# Sheet1.net
KiCad netlist of a schematic drawn in Altium Designer
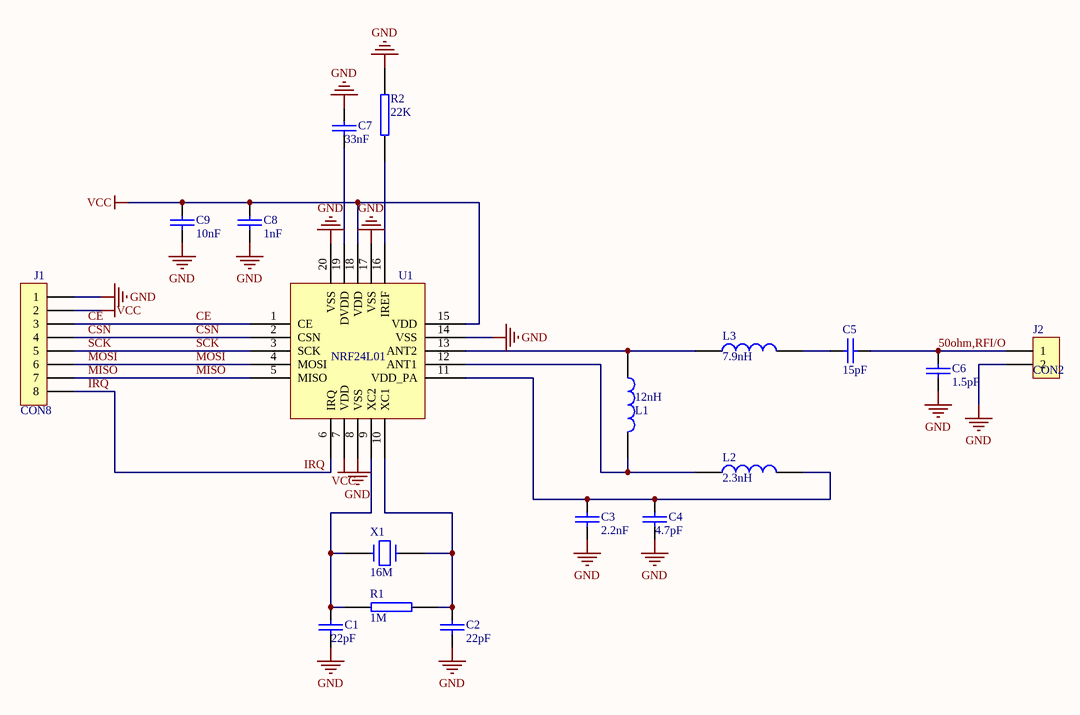
[diagram p0: Sheet1.SchDoc]

(export (version "E")
  (design (tool "Eeschema 10.0.6"))
  (components
    (comp (ref "C1")
      (value "22pF")
      (footprint "1608[0603]")
      (description "Capacitor")
      (libsource (lib "*") (part "CAP"))
    )
    (comp (ref "C2")
      (value "22pF")
      (footprint "1608[0603]")
      (description "Capacitor")
      (libsource (lib "*") (part "CAP"))
    )
    (comp (ref "C3")
      (value "2.2nF")
      (footprint "1608[0603]")
      (description "Capacitor")
      (libsource (lib "*") (part "CAP"))
    )
    (comp (ref "C4")
      (value "4.7pF")
      (footprint "1608[0603]")
      (description "Capacitor")
      (libsource (lib "*") (part "CAP"))
    )
    (comp (ref "C5")
      (value "15pF")
      (footprint "1608[0603]")
      (description "Capacitor")
      (libsource (lib "*") (part "CAP"))
    )
    (comp (ref "C6")
      (value "1.5pF")
      (footprint "1608[0603]")
      (description "Capacitor")
      (libsource (lib "*") (part "CAP"))
    )
    (comp (ref "C7")
      (value "33nF")
      (footprint "Miscellaneous Devices:1608[0603]")
      (description "Capacitor")
      (libsource (lib "*") (part "CAP"))
    )
    (comp (ref "C8")
      (value "1nF")
      (footprint "1608[0603]")
      (description "Capacitor")
      (libsource (lib "*") (part "CAP"))
    )
    (comp (ref "C9")
      (value "10nF")
      (footprint "1608[0603]")
      (description "Capacitor")
      (libsource (lib "*") (part "CAP"))
    )
    (comp (ref "J1")
      (value "CON8")
      (footprint "HDR2X4")
      (description "Connector")
      (libsource (lib "*") (part "CON8"))
    )
    (comp (ref "J2")
      (value "CON2")
      (footprint "SMA")
      (description "Connector")
      (libsource (lib "*") (part "CON2"))
    )
    (comp (ref "L1") (value "12nH") (footprint "1608[0603]") (libsource (lib "*") (part "INDUCTOR")))
    (comp (ref "L2") (value "2.3nH") (footprint "1608[0603]") (libsource (lib "*") (part "INDUCTOR")))
    (comp (ref "L3") (value "7.9nH") (footprint "1608[0603]") (libsource (lib "*") (part "INDUCTOR")))
    (comp (ref "R1") (value "1M") (footprint "1608[0603]") (libsource (lib "*") (part "RES2")))
    (comp (ref "R2") (value "22K") (footprint "1608[0603]") (libsource (lib "*") (part "RES2")))
    (comp (ref "U1") (value "NRF24L01") (footprint "传感器fsc:wifi") (libsource (lib "*") (part "NRF24L01")))
    (comp (ref "X1")
      (value "16M")
      (footprint "传感器fsc:jingzhen")
      (description "Crystal")
      (libsource (lib "*") (part "CRYSTAL"))
    )
  )
  (nets
    (net (code "1") (name "/50ohm,RFI{slash}O") (class "Default")
      (node (ref "C5") (pin "2") (pinfunction "2_2") (pintype "passive"))
      (node (ref "C6") (pin "1") (pinfunction "1_1") (pintype "passive"))
      (node (ref "J2") (pin "1") (pinfunction "1_1") (pintype "passive"))
    )
    (net (code "2") (name "/CE") (class "Default")
      (node (ref "J1") (pin "3") (pinfunction "3_3") (pintype "passive"))
      (node (ref "U1") (pin "1") (pinfunction "CE_1") (pintype "passive"))
    )
    (net (code "3") (name "/CSN") (class "Default")
      (node (ref "J1") (pin "4") (pinfunction "4_4") (pintype "passive"))
      (node (ref "U1") (pin "2") (pinfunction "CSN_2") (pintype "passive"))
    )
    (net (code "4") (name "/IRQ") (class "Default")
      (node (ref "J1") (pin "8") (pinfunction "8_8") (pintype "passive"))
      (node (ref "U1") (pin "6") (pinfunction "IRQ_6") (pintype "passive"))
    )
    (net (code "5") (name "/MISO") (class "Default")
      (node (ref "J1") (pin "7") (pinfunction "7_7") (pintype "passive"))
      (node (ref "U1") (pin "5") (pinfunction "MISO_5") (pintype "passive"))
    )
    (net (code "6") (name "/MOSI") (class "Default")
      (node (ref "J1") (pin "6") (pinfunction "6_6") (pintype "passive"))
      (node (ref "U1") (pin "4") (pinfunction "MOSI_4") (pintype "passive"))
    )
    (net (code "7") (name "/SCK") (class "Default")
      (node (ref "J1") (pin "5") (pinfunction "5_5") (pintype "passive"))
      (node (ref "U1") (pin "3") (pinfunction "SCK_3") (pintype "passive"))
    )
    (net (code "8") (name "GND") (class "Default")
      (node (ref "C1") (pin "2") (pinfunction "2_2") (pintype "passive"))
      (node (ref "C2") (pin "2") (pinfunction "2_2") (pintype "passive"))
      (node (ref "C3") (pin "2") (pinfunction "2_2") (pintype "passive"))
      (node (ref "C4") (pin "2") (pinfunction "2_2") (pintype "passive"))
      (node (ref "C6") (pin "2") (pinfunction "2_2") (pintype "passive"))
      (node (ref "C7") (pin "1") (pinfunction "1_1") (pintype "passive"))
      (node (ref "C8") (pin "2") (pinfunction "2_2") (pintype "passive"))
      (node (ref "C9") (pin "2") (pinfunction "2_2") (pintype "passive"))
      (node (ref "J1") (pin "1") (pinfunction "1_1") (pintype "passive"))
      (node (ref "J2") (pin "2") (pinfunction "2_2") (pintype "passive"))
      (node (ref "R2") (pin "2") (pinfunction "2_2") (pintype "passive"))
      (node (ref "U1") (pin "14") (pinfunction "VSS_14") (pintype "passive"))
      (node (ref "U1") (pin "17") (pinfunction "VSS_17") (pintype "passive"))
      (node (ref "U1") (pin "20") (pinfunction "VSS_20") (pintype "passive"))
      (node (ref "U1") (pin "8") (pinfunction "VSS_8") (pintype "passive"))
    )
    (net (code "9") (name "Net-(C5-Pad1)") (class "Default")
      (node (ref "C5") (pin "1") (pinfunction "1_1") (pintype "passive"))
      (node (ref "L3") (pin "2") (pinfunction "2_2") (pintype "passive"))
    )
    (net (code "10") (name "Net-(U1-ANT1)") (class "Default")
      (node (ref "L1") (pin "2") (pinfunction "2_2") (pintype "passive"))
      (node (ref "L2") (pin "1") (pinfunction "1_1") (pintype "passive"))
      (node (ref "U1") (pin "12") (pinfunction "ANT1_12") (pintype "passive"))
    )
    (net (code "11") (name "Net-(U1-ANT2)") (class "Default")
      (node (ref "L1") (pin "1") (pinfunction "1_1") (pintype "passive"))
      (node (ref "L3") (pin "1") (pinfunction "1_1") (pintype "passive"))
      (node (ref "U1") (pin "13") (pinfunction "ANT2_13") (pintype "passive"))
    )
    (net (code "12") (name "Net-(U1-DVDD)") (class "Default")
      (node (ref "C7") (pin "2") (pinfunction "2_2") (pintype "passive"))
      (node (ref "U1") (pin "19") (pinfunction "DVDD_19") (pintype "passive"))
    )
    (net (code "13") (name "Net-(U1-IREF)") (class "Default")
      (node (ref "R2") (pin "1") (pinfunction "1_1") (pintype "passive"))
      (node (ref "U1") (pin "16") (pinfunction "IREF_16") (pintype "passive"))
    )
    (net (code "14") (name "Net-(U1-VDD_PA)") (class "Default")
      (node (ref "C3") (pin "1") (pinfunction "1_1") (pintype "passive"))
      (node (ref "C4") (pin "1") (pinfunction "1_1") (pintype "passive"))
      (node (ref "L2") (pin "2") (pinfunction "2_2") (pintype "passive"))
      (node (ref "U1") (pin "11") (pinfunction "VDD_PA_11") (pintype "passive"))
    )
    (net (code "15") (name "Net-(U1-XC1)") (class "Default")
      (node (ref "C2") (pin "1") (pinfunction "1_1") (pintype "passive"))
      (node (ref "R1") (pin "2") (pinfunction "2_2") (pintype "passive"))
      (node (ref "U1") (pin "10") (pinfunction "XC1_10") (pintype "passive"))
      (node (ref "X1") (pin "2") (pinfunction "2_2") (pintype "passive"))
    )
    (net (code "16") (name "Net-(U1-XC2)") (class "Default")
      (node (ref "C1") (pin "1") (pinfunction "1_1") (pintype "passive"))
      (node (ref "R1") (pin "1") (pinfunction "1_1") (pintype "passive"))
      (node (ref "U1") (pin "9") (pinfunction "XC2_9") (pintype "passive"))
      (node (ref "X1") (pin "1") (pinfunction "1_1") (pintype "passive"))
    )
    (net (code "17") (name "VCC") (class "Default")
      (node (ref "C8") (pin "1") (pinfunction "1_1") (pintype "passive"))
      (node (ref "C9") (pin "1") (pinfunction "1_1") (pintype "passive"))
      (node (ref "J1") (pin "2") (pinfunction "2_2") (pintype "passive"))
      (node (ref "U1") (pin "15") (pinfunction "VDD_15") (pintype "passive"))
      (node (ref "U1") (pin "18") (pinfunction "VDD_18") (pintype "passive"))
      (node (ref "U1") (pin "7") (pinfunction "VDD_7") (pintype "passive"))
    )
  )
)
